# Imager_Mainboard.net
KiCad netlist of a schematic drawn in EAGLE
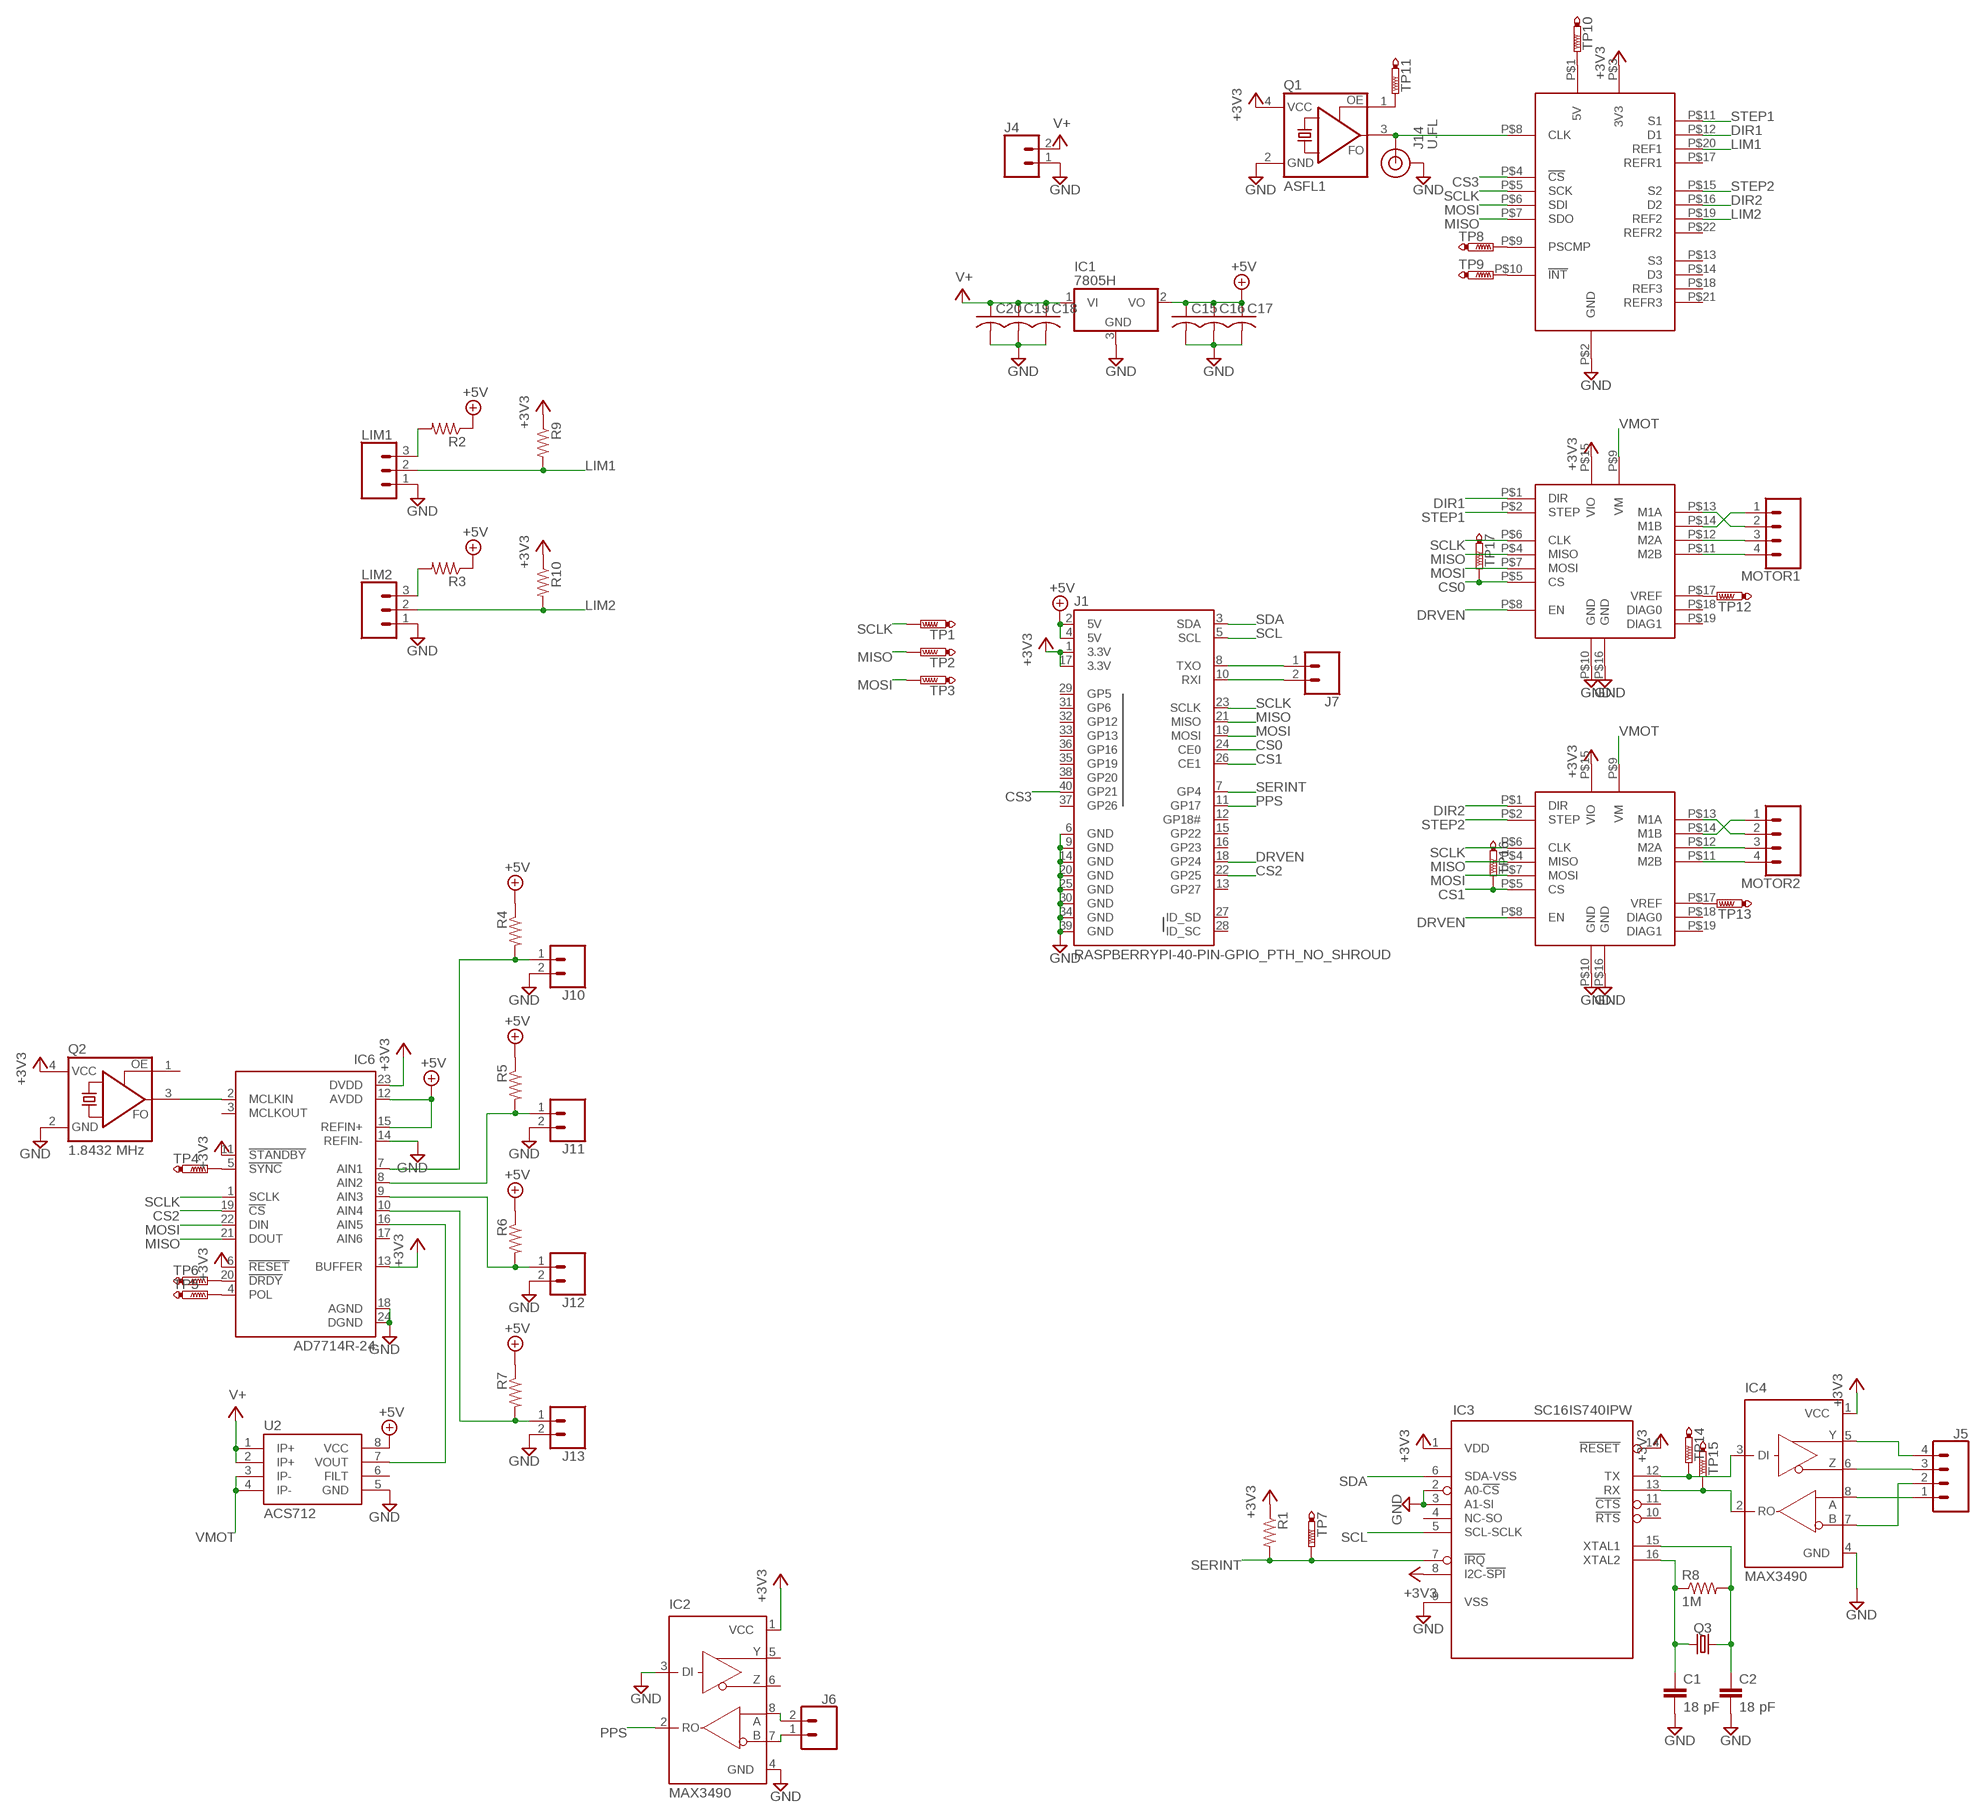
[diagram p0: schematic, sheet 1]

(export (version "E")
  (design (tool "Eeschema 10.0.6"))
  (components
    (comp (ref "C1")
      (value "18 pF")
      (footprint "eagle-import:C1206")
      (libsource (lib "eagle-import") (part "C-EUC1206"))
    )
    (comp (ref "C2")
      (value "18 pF")
      (footprint "eagle-import:C1206")
      (libsource (lib "eagle-import") (part "C-EUC1206"))
    )
    (comp (ref "C15")
      (value "C-USC1206")
      (footprint "eagle-import:C1206")
      (libsource (lib "eagle-import") (part "C-USC1206"))
    )
    (comp (ref "C16")
      (value "C-USC1206")
      (footprint "eagle-import:C1206")
      (libsource (lib "eagle-import") (part "C-USC1206"))
    )
    (comp (ref "C17")
      (value "C-USC1206")
      (footprint "eagle-import:C1206")
      (libsource (lib "eagle-import") (part "C-USC1206"))
    )
    (comp (ref "C18")
      (value "C-USC1206")
      (footprint "eagle-import:C1206")
      (libsource (lib "eagle-import") (part "C-USC1206"))
    )
    (comp (ref "C19")
      (value "C-USC1206")
      (footprint "eagle-import:C1206")
      (libsource (lib "eagle-import") (part "C-USC1206"))
    )
    (comp (ref "C20")
      (value "C-USC1206")
      (footprint "eagle-import:C1206")
      (libsource (lib "eagle-import") (part "C-USC1206"))
    )
    (comp (ref "DRV1")
      (value "SILENTSTEPSTICK")
      (footprint "eagle-import:SILENTSTEPSTICK")
      (libsource (lib "eagle-import") (part "SILENTSTEPSTICK"))
    )
    (comp (ref "DRV2")
      (value "SILENTSTEPSTICK")
      (footprint "eagle-import:SILENTSTEPSTICK")
      (libsource (lib "eagle-import") (part "SILENTSTEPSTICK"))
    )
    (comp (ref "IC1")
      (value "7805H")
      (footprint "eagle-import:TO39")
      (libsource (lib "eagle-import") (part "78H05"))
    )
    (comp (ref "IC2")
      (value "MAX3490")
      (footprint "eagle-import:SO08")
      (libsource (lib "eagle-import") (part "MAX3467PAC"))
    )
    (comp (ref "IC3")
      (value "SC16IS740IPW")
      (footprint "eagle-import:TSSOP16L")
      (libsource (lib "eagle-import") (part "SC16IS740IPW"))
    )
    (comp (ref "IC4")
      (value "MAX3490")
      (footprint "eagle-import:SO08")
      (libsource (lib "eagle-import") (part "MAX3467PAC"))
    )
    (comp (ref "IC6")
      (value "AD7714R-24")
      (footprint "eagle-import:SO24R")
      (libsource (lib "eagle-import") (part "AD7714R-24"))
    )
    (comp (ref "J1")
      (value "RASPBERRYPI-40-PIN-GPIO_PTH_NO_SHROUD")
      (footprint "eagle-import:2X20")
      (libsource (lib "eagle-import") (part "RASPBERRYPI-40-PIN-GPIO_PTH_NO_SHROUD"))
    )
    (comp (ref "J4")
      (value "CONN_02")
      (footprint "eagle-import:1X02")
      (libsource (lib "eagle-import") (part "CONN_02"))
    )
    (comp (ref "J5")
      (value "CONN_04")
      (footprint "eagle-import:1X04")
      (libsource (lib "eagle-import") (part "CONN_04"))
    )
    (comp (ref "J6")
      (value "CONN_02")
      (footprint "eagle-import:1X02")
      (libsource (lib "eagle-import") (part "CONN_02"))
    )
    (comp (ref "J7")
      (value "CONN_02")
      (footprint "eagle-import:1X02")
      (libsource (lib "eagle-import") (part "CONN_02"))
    )
    (comp (ref "J10")
      (value "CONN_02")
      (footprint "eagle-import:1X02")
      (libsource (lib "eagle-import") (part "CONN_02"))
    )
    (comp (ref "J11")
      (value "CONN_02")
      (footprint "eagle-import:1X02")
      (libsource (lib "eagle-import") (part "CONN_02"))
    )
    (comp (ref "J12")
      (value "CONN_02")
      (footprint "eagle-import:1X02")
      (libsource (lib "eagle-import") (part "CONN_02"))
    )
    (comp (ref "J13")
      (value "CONN_02")
      (footprint "eagle-import:1X02")
      (libsource (lib "eagle-import") (part "CONN_02"))
    )
    (comp (ref "J14")
      (value "U.FL")
      (footprint "eagle-import:U.FL")
      (libsource (lib "eagle-import") (part "U.FL2PIN"))
    )
    (comp (ref "LIM1")
      (value "CONN_03")
      (footprint "eagle-import:1X03")
      (libsource (lib "eagle-import") (part "CONN_03"))
    )
    (comp (ref "LIM2")
      (value "CONN_03")
      (footprint "eagle-import:1X03")
      (libsource (lib "eagle-import") (part "CONN_03"))
    )
    (comp (ref "MOTOR1")
      (value "CONN_04")
      (footprint "eagle-import:1X04")
      (libsource (lib "eagle-import") (part "CONN_04"))
    )
    (comp (ref "MOTOR2")
      (value "CONN_04")
      (footprint "eagle-import:1X04")
      (libsource (lib "eagle-import") (part "CONN_04"))
    )
    (comp (ref "Q1")
      (value "ASFL1")
      (footprint "eagle-import:ASF")
      (fields (field (name "MF") "Abracon Corporation") (field (name "MPN") "ASFL1-125.000MHZ-EC-T"))
      (libsource (lib "eagle-import") (part "ASFL1"))
    )
    (comp (ref "Q2")
      (value "1.8432 MHz")
      (footprint "eagle-import:ASF")
      (fields (field (name "MF") "Abracon Corporation") (field (name "MPN") "ASFL1-125.000MHZ-EC-T"))
      (libsource (lib "eagle-import") (part "ASFL1"))
    )
    (comp (ref "Q3")
      (value "CRYSTALSMD-5X3.2-4PAD")
      (footprint "eagle-import:CRYSTAL-SMD-5X3.2-4PAD")
      (libsource (lib "eagle-import") (part "CRYSTALSMD-5X3.2-4PAD"))
    )
    (comp (ref "R1")
      (value "R-US_R1206")
      (footprint "eagle-import:R1206")
      (libsource (lib "eagle-import") (part "R-US_R1206"))
    )
    (comp (ref "R2")
      (value "R-US_R1206")
      (footprint "eagle-import:R1206")
      (libsource (lib "eagle-import") (part "R-US_R1206"))
    )
    (comp (ref "R3")
      (value "R-US_R1206")
      (footprint "eagle-import:R1206")
      (libsource (lib "eagle-import") (part "R-US_R1206"))
    )
    (comp (ref "R4")
      (value "R-US_R1206")
      (footprint "eagle-import:R1206")
      (libsource (lib "eagle-import") (part "R-US_R1206"))
    )
    (comp (ref "R5")
      (value "R-US_R1206")
      (footprint "eagle-import:R1206")
      (libsource (lib "eagle-import") (part "R-US_R1206"))
    )
    (comp (ref "R6")
      (value "R-US_R1206")
      (footprint "eagle-import:R1206")
      (libsource (lib "eagle-import") (part "R-US_R1206"))
    )
    (comp (ref "R7")
      (value "R-US_R1206")
      (footprint "eagle-import:R1206")
      (libsource (lib "eagle-import") (part "R-US_R1206"))
    )
    (comp (ref "R8")
      (value "1M")
      (footprint "eagle-import:R1206")
      (libsource (lib "eagle-import") (part "R-US_R1206"))
    )
    (comp (ref "R9")
      (value "R-US_R1206")
      (footprint "eagle-import:R1206")
      (libsource (lib "eagle-import") (part "R-US_R1206"))
    )
    (comp (ref "R10")
      (value "R-US_R1206")
      (footprint "eagle-import:R1206")
      (libsource (lib "eagle-import") (part "R-US_R1206"))
    )
    (comp (ref "TP1")
      (value "PTR1PAD1-13")
      (footprint "eagle-import:P1-13")
      (libsource (lib "eagle-import") (part "PTR1PAD1-13"))
    )
    (comp (ref "TP2")
      (value "PTR1PAD1-13")
      (footprint "eagle-import:P1-13")
      (libsource (lib "eagle-import") (part "PTR1PAD1-13"))
    )
    (comp (ref "TP3")
      (value "PTR1PAD1-13")
      (footprint "eagle-import:P1-13")
      (libsource (lib "eagle-import") (part "PTR1PAD1-13"))
    )
    (comp (ref "TP4")
      (value "PTR1B1,27")
      (footprint "eagle-import:B1,27")
      (libsource (lib "eagle-import") (part "PTR1B1,27"))
    )
    (comp (ref "TP5")
      (value "PTR1B1,27")
      (footprint "eagle-import:B1,27")
      (libsource (lib "eagle-import") (part "PTR1B1,27"))
    )
    (comp (ref "TP6")
      (value "PTR1B1,27")
      (footprint "eagle-import:B1,27")
      (libsource (lib "eagle-import") (part "PTR1B1,27"))
    )
    (comp (ref "TP7")
      (value "PTR1B1,27")
      (footprint "eagle-import:B1,27")
      (libsource (lib "eagle-import") (part "PTR1B1,27"))
    )
    (comp (ref "TP8")
      (value "PTR1PAD1-13")
      (footprint "eagle-import:P1-13")
      (libsource (lib "eagle-import") (part "PTR1PAD1-13"))
    )
    (comp (ref "TP9")
      (value "PTR1PAD1-13")
      (footprint "eagle-import:P1-13")
      (libsource (lib "eagle-import") (part "PTR1PAD1-13"))
    )
    (comp (ref "TP10")
      (value "PTR1PAD1-13")
      (footprint "eagle-import:P1-13")
      (libsource (lib "eagle-import") (part "PTR1PAD1-13"))
    )
    (comp (ref "TP11")
      (value "PTR1PAD1-13")
      (footprint "eagle-import:P1-13")
      (libsource (lib "eagle-import") (part "PTR1PAD1-13"))
    )
    (comp (ref "TP12")
      (value "PTR1PAD1-13")
      (footprint "eagle-import:P1-13")
      (libsource (lib "eagle-import") (part "PTR1PAD1-13"))
    )
    (comp (ref "TP13")
      (value "PTR1PAD1-13")
      (footprint "eagle-import:P1-13")
      (libsource (lib "eagle-import") (part "PTR1PAD1-13"))
    )
    (comp (ref "TP14")
      (value "PTR1PAD1-13")
      (footprint "eagle-import:P1-13")
      (libsource (lib "eagle-import") (part "PTR1PAD1-13"))
    )
    (comp (ref "TP15")
      (value "PTR1PAD1-13")
      (footprint "eagle-import:P1-13")
      (libsource (lib "eagle-import") (part "PTR1PAD1-13"))
    )
    (comp (ref "TP16")
      (value "PTR1PAD1-13")
      (footprint "eagle-import:P1-13")
      (libsource (lib "eagle-import") (part "PTR1PAD1-13"))
    )
    (comp (ref "TP17")
      (value "PTR1PAD1-13")
      (footprint "eagle-import:P1-13")
      (libsource (lib "eagle-import") (part "PTR1PAD1-13"))
    )
    (comp (ref "U$1")
      (value "TMC429-BOB")
      (footprint "eagle-import:TMC429-BOB")
      (libsource (lib "eagle-import") (part "TMC429-BOB"))
    )
    (comp (ref "U2")
      (value "ACS712")
      (footprint "eagle-import:SO08")
      (libsource (lib "eagle-import") (part "ACS712"))
    )
  )
  (nets
    (net (code "1") (name "+3V3") (class "Default")
      (node (ref "DRV1") (pin "P$15") (pinfunction "VIO_P$15") (pintype "bidirectional"))
      (node (ref "DRV2") (pin "P$15") (pinfunction "VIO_P$15") (pintype "bidirectional"))
      (node (ref "IC2") (pin "1") (pinfunction "VCC_1") (pintype "power_in"))
      (node (ref "IC3") (pin "1") (pinfunction "VDD_1") (pintype "bidirectional"))
      (node (ref "IC3") (pin "14") (pinfunction "~{RESET}_14") (pintype "bidirectional"))
      (node (ref "IC3") (pin "8") (pinfunction "I2C-~{SPI}_8") (pintype "bidirectional"))
      (node (ref "IC4") (pin "1") (pinfunction "VCC_1") (pintype "power_in"))
      (node (ref "IC6") (pin "11") (pinfunction "~{STANDBY}_11") (pintype "input"))
      (node (ref "IC6") (pin "13") (pinfunction "BUFFER_13") (pintype "input"))
      (node (ref "IC6") (pin "23") (pinfunction "DVDD_23") (pintype "input"))
      (node (ref "IC6") (pin "6") (pinfunction "~{RESET}_6") (pintype "input"))
      (node (ref "J1") (pin "1") (pinfunction "3.3V_1") (pintype "power_in"))
      (node (ref "J1") (pin "17") (pinfunction "3.3V_17") (pintype "power_in"))
      (node (ref "Q1") (pin "4") (pinfunction "VCC_4") (pintype "power_in"))
      (node (ref "Q2") (pin "4") (pinfunction "VCC_4") (pintype "power_in"))
      (node (ref "R1") (pin "1") (pinfunction "1_1") (pintype "passive"))
      (node (ref "R10") (pin "1") (pinfunction "1_1") (pintype "passive"))
      (node (ref "R9") (pin "1") (pinfunction "1_1") (pintype "passive"))
      (node (ref "U$1") (pin "P$3") (pinfunction "3V3_P$3") (pintype "bidirectional"))
    )
    (net (code "2") (name "+5V") (class "Default")
      (node (ref "C15") (pin "1") (pinfunction "1_1") (pintype "passive"))
      (node (ref "C16") (pin "1") (pinfunction "1_1") (pintype "passive"))
      (node (ref "C17") (pin "1") (pinfunction "1_1") (pintype "passive"))
      (node (ref "IC1") (pin "2") (pinfunction "VO_2") (pintype "passive"))
      (node (ref "IC6") (pin "12") (pinfunction "AVDD_12") (pintype "input"))
      (node (ref "IC6") (pin "15") (pinfunction "REFIN+_15") (pintype "input"))
      (node (ref "J1") (pin "2") (pinfunction "5V_2") (pintype "power_in"))
      (node (ref "J1") (pin "4") (pinfunction "5V_4") (pintype "power_in"))
      (node (ref "R2") (pin "1") (pinfunction "1_1") (pintype "passive"))
      (node (ref "R3") (pin "1") (pinfunction "1_1") (pintype "passive"))
      (node (ref "R4") (pin "1") (pinfunction "1_1") (pintype "passive"))
      (node (ref "R5") (pin "1") (pinfunction "1_1") (pintype "passive"))
      (node (ref "R6") (pin "1") (pinfunction "1_1") (pintype "passive"))
      (node (ref "R7") (pin "1") (pinfunction "1_1") (pintype "passive"))
      (node (ref "U2") (pin "8") (pinfunction "VCC_8") (pintype "bidirectional"))
    )
    (net (code "3") (name "/CS0") (class "Default")
      (node (ref "DRV1") (pin "P$5") (pinfunction "CS_P$5") (pintype "bidirectional"))
      (node (ref "J1") (pin "24") (pinfunction "CE0_24") (pintype "output"))
      (node (ref "TP17") (pin "TP") (pinfunction "TP_TP") (pintype "input"))
    )
    (net (code "4") (name "/CS1") (class "Default")
      (node (ref "DRV2") (pin "P$5") (pinfunction "CS_P$5") (pintype "bidirectional"))
      (node (ref "J1") (pin "26") (pinfunction "CE1_26") (pintype "output"))
      (node (ref "TP16") (pin "TP") (pinfunction "TP_TP") (pintype "input"))
    )
    (net (code "5") (name "/CS2") (class "Default")
      (node (ref "IC6") (pin "19") (pinfunction "~{CS}_19") (pintype "input"))
      (node (ref "J1") (pin "22") (pinfunction "GP25_22") (pintype "bidirectional"))
    )
    (net (code "6") (name "/CS3") (class "Default")
      (node (ref "J1") (pin "40") (pinfunction "GP21_40") (pintype "bidirectional"))
      (node (ref "U$1") (pin "P$4") (pinfunction "~{CS}_P$4") (pintype "bidirectional"))
    )
    (net (code "7") (name "/DIR1") (class "Default")
      (node (ref "DRV1") (pin "P$1") (pinfunction "DIR_P$1") (pintype "bidirectional"))
      (node (ref "U$1") (pin "P$12") (pinfunction "D1_P$12") (pintype "bidirectional"))
    )
    (net (code "8") (name "/DIR2") (class "Default")
      (node (ref "DRV2") (pin "P$1") (pinfunction "DIR_P$1") (pintype "bidirectional"))
      (node (ref "U$1") (pin "P$16") (pinfunction "D2_P$16") (pintype "bidirectional"))
    )
    (net (code "9") (name "/DRVEN") (class "Default")
      (node (ref "DRV1") (pin "P$8") (pinfunction "EN_P$8") (pintype "bidirectional"))
      (node (ref "DRV2") (pin "P$8") (pinfunction "EN_P$8") (pintype "bidirectional"))
      (node (ref "J1") (pin "18") (pinfunction "GP24_18") (pintype "bidirectional"))
    )
    (net (code "10") (name "/LIM1") (class "Default")
      (node (ref "LIM1") (pin "2") (pinfunction "2_2") (pintype "passive"))
      (node (ref "R9") (pin "2") (pinfunction "2_2") (pintype "passive"))
      (node (ref "U$1") (pin "P$20") (pinfunction "REF1_P$20") (pintype "bidirectional"))
    )
    (net (code "11") (name "/LIM2") (class "Default")
      (node (ref "LIM2") (pin "2") (pinfunction "2_2") (pintype "passive"))
      (node (ref "R10") (pin "2") (pinfunction "2_2") (pintype "passive"))
      (node (ref "U$1") (pin "P$19") (pinfunction "REF2_P$19") (pintype "bidirectional"))
    )
    (net (code "12") (name "/MISO") (class "Default")
      (node (ref "DRV1") (pin "P$4") (pinfunction "MISO_P$4") (pintype "bidirectional"))
      (node (ref "DRV2") (pin "P$4") (pinfunction "MISO_P$4") (pintype "bidirectional"))
      (node (ref "IC6") (pin "21") (pinfunction "DOUT_21") (pintype "output"))
      (node (ref "J1") (pin "21") (pinfunction "MISO_21") (pintype "input"))
      (node (ref "TP2") (pin "TP") (pinfunction "TP_TP") (pintype "input"))
      (node (ref "U$1") (pin "P$7") (pinfunction "SDO_P$7") (pintype "bidirectional"))
    )
    (net (code "13") (name "/MOSI") (class "Default")
      (node (ref "DRV1") (pin "P$7") (pinfunction "MOSI_P$7") (pintype "bidirectional"))
      (node (ref "DRV2") (pin "P$7") (pinfunction "MOSI_P$7") (pintype "bidirectional"))
      (node (ref "IC6") (pin "22") (pinfunction "DIN_22") (pintype "input"))
      (node (ref "J1") (pin "19") (pinfunction "MOSI_19") (pintype "output"))
      (node (ref "TP3") (pin "TP") (pinfunction "TP_TP") (pintype "input"))
      (node (ref "U$1") (pin "P$6") (pinfunction "SDI_P$6") (pintype "bidirectional"))
    )
    (net (code "14") (name "/PPS") (class "Default")
      (node (ref "IC2") (pin "2") (pinfunction "RO_2") (pintype "output"))
      (node (ref "J1") (pin "11") (pinfunction "GP17_11") (pintype "bidirectional"))
    )
    (net (code "15") (name "/SCL") (class "Default")
      (node (ref "IC3") (pin "5") (pinfunction "SCL-SCLK_5") (pintype "bidirectional"))
      (node (ref "J1") (pin "5") (pinfunction "SCL_5") (pintype "bidirectional"))
    )
    (net (code "16") (name "/SCLK") (class "Default")
      (node (ref "DRV1") (pin "P$6") (pinfunction "CLK_P$6") (pintype "bidirectional"))
      (node (ref "DRV2") (pin "P$6") (pinfunction "CLK_P$6") (pintype "bidirectional"))
      (node (ref "IC6") (pin "1") (pinfunction "SCLK_1") (pintype "input"))
      (node (ref "J1") (pin "23") (pinfunction "SCLK_23") (pintype "output"))
      (node (ref "TP1") (pin "TP") (pinfunction "TP_TP") (pintype "input"))
      (node (ref "U$1") (pin "P$5") (pinfunction "SCK_P$5") (pintype "bidirectional"))
    )
    (net (code "17") (name "/SDA") (class "Default")
      (node (ref "IC3") (pin "6") (pinfunction "SDA-VSS_6") (pintype "bidirectional"))
      (node (ref "J1") (pin "3") (pinfunction "SDA_3") (pintype "bidirectional"))
    )
    (net (code "18") (name "/SERINT") (class "Default")
      (node (ref "IC3") (pin "7") (pinfunction "~{IRQ}_7") (pintype "bidirectional"))
      (node (ref "J1") (pin "7") (pinfunction "GP4_7") (pintype "bidirectional"))
      (node (ref "R1") (pin "2") (pinfunction "2_2") (pintype "passive"))
      (node (ref "TP7") (pin "TP") (pinfunction "TP_TP") (pintype "input"))
    )
    (net (code "19") (name "/STEP1") (class "Default")
      (node (ref "DRV1") (pin "P$2") (pinfunction "STEP_P$2") (pintype "bidirectional"))
      (node (ref "U$1") (pin "P$11") (pinfunction "S1_P$11") (pintype "bidirectional"))
    )
    (net (code "20") (name "/STEP2") (class "Default")
      (node (ref "DRV2") (pin "P$2") (pinfunction "STEP_P$2") (pintype "bidirectional"))
      (node (ref "U$1") (pin "P$15") (pinfunction "S2_P$15") (pintype "bidirectional"))
    )
    (net (code "21") (name "/VMOT") (class "Default")
      (node (ref "DRV1") (pin "P$9") (pinfunction "VM_P$9") (pintype "bidirectional"))
      (node (ref "DRV2") (pin "P$9") (pinfunction "VM_P$9") (pintype "bidirectional"))
      (node (ref "U2") (pin "3") (pinfunction "IP-_3") (pintype "bidirectional"))
      (node (ref "U2") (pin "4") (pinfunction "IP-_4") (pintype "bidirectional"))
    )
    (net (code "22") (name "GND") (class "Default")
      (node (ref "C1") (pin "2") (pinfunction "2_2") (pintype "passive"))
      (node (ref "C15") (pin "2") (pinfunction "2_2") (pintype "passive"))
      (node (ref "C16") (pin "2") (pinfunction "2_2") (pintype "passive"))
      (node (ref "C17") (pin "2") (pinfunction "2_2") (pintype "passive"))
      (node (ref "C18") (pin "2") (pinfunction "2_2") (pintype "passive"))
      (node (ref "C19") (pin "2") (pinfunction "2_2") (pintype "passive"))
      (node (ref "C2") (pin "2") (pinfunction "2_2") (pintype "passive"))
      (node (ref "C20") (pin "2") (pinfunction "2_2") (pintype "passive"))
      (node (ref "DRV1") (pin "P$10") (pinfunction "GND_P$10") (pintype "bidirectional"))
      (node (ref "DRV1") (pin "P$16") (pinfunction "GND_P$16") (pintype "bidirectional"))
      (node (ref "DRV2") (pin "P$10") (pinfunction "GND_P$10") (pintype "bidirectional"))
      (node (ref "DRV2") (pin "P$16") (pinfunction "GND_P$16") (pintype "bidirectional"))
      (node (ref "IC1") (pin "3") (pinfunction "GND_3") (pintype "passive"))
      (node (ref "IC2") (pin "3") (pinfunction "DI_3") (pintype "input"))
      (node (ref "IC2") (pin "4") (pinfunction "GND_4") (pintype "power_in"))
      (node (ref "IC3") (pin "2") (pinfunction "A0-~{CS}_2") (pintype "bidirectional"))
      (node (ref "IC3") (pin "3") (pinfunction "A1-SI_3") (pintype "bidirectional"))
      (node (ref "IC3") (pin "9") (pinfunction "VSS_9") (pintype "bidirectional"))
      (node (ref "IC4") (pin "4") (pinfunction "GND_4") (pintype "power_in"))
      (node (ref "IC6") (pin "14") (pinfunction "REFIN-_14") (pintype "input"))
      (node (ref "IC6") (pin "18") (pinfunction "AGND_18") (pintype "input"))
      (node (ref "IC6") (pin "24") (pinfunction "DGND_24") (pintype "input"))
      (node (ref "J1") (pin "14") (pinfunction "GND_14") (pintype "power_in"))
      (node (ref "J1") (pin "20") (pinfunction "GND_20") (pintype "power_in"))
      (node (ref "J1") (pin "25") (pinfunction "GND_25") (pintype "power_in"))
      (node (ref "J1") (pin "30") (pinfunction "GND_30") (pintype "power_in"))
      (node (ref "J1") (pin "34") (pinfunction "GND_34") (pintype "power_in"))
      (node (ref "J1") (pin "39") (pinfunction "GND_39") (pintype "power_in"))
      (node (ref "J1") (pin "6") (pinfunction "GND_6") (pintype "power_in"))
      (node (ref "J1") (pin "9") (pinfunction "GND_9") (pintype "power_in"))
      (node (ref "J10") (pin "2") (pinfunction "2_2") (pintype "passive"))
      (node (ref "J11") (pin "2") (pinfunction "2_2") (pintype "passive"))
      (node (ref "J12") (pin "2") (pinfunction "2_2") (pintype "passive"))
      (node (ref "J13") (pin "2") (pinfunction "2_2") (pintype "passive"))
      (node (ref "J14") (pin "1") (pinfunction "GND_1") (pintype "bidirectional"))
      (node (ref "J14") (pin "2") (pinfunction "GND_2") (pintype "bidirectional"))
      (node (ref "J4") (pin "1") (pinfunction "1_1") (pintype "passive"))
      (node (ref "LIM1") (pin "1") (pinfunction "1_1") (pintype "passive"))
      (node (ref "LIM2") (pin "1") (pinfunction "1_1") (pintype "passive"))
      (node (ref "Q1") (pin "2") (pinfunction "GND_2") (pintype "power_in"))
      (node (ref "Q2") (pin "2") (pinfunction "GND_2") (pintype "power_in"))
      (node (ref "U$1") (pin "P$2") (pinfunction "GND_P$2") (pintype "bidirectional"))
      (node (ref "U2") (pin "5") (pinfunction "GND_5") (pintype "bidirectional"))
    )
    (net (code "23") (name "Net-(DRV1-M1A)") (class "Default")
      (node (ref "DRV1") (pin "P$13") (pinfunction "M1A_P$13") (pintype "bidirectional"))
      (node (ref "MOTOR1") (pin "2") (pinfunction "2_2") (pintype "passive"))
    )
    (net (code "24") (name "Net-(DRV1-M1B)") (class "Default")
      (node (ref "DRV1") (pin "P$14") (pinfunction "M1B_P$14") (pintype "bidirectional"))
      (node (ref "MOTOR1") (pin "1") (pinfunction "1_1") (pintype "passive"))
    )
    (net (code "25") (name "Net-(DRV1-M2A)") (class "Default")
      (node (ref "DRV1") (pin "P$12") (pinfunction "M2A_P$12") (pintype "bidirectional"))
      (node (ref "MOTOR1") (pin "3") (pinfunction "3_3") (pintype "passive"))
    )
    (net (code "26") (name "Net-(DRV1-M2B)") (class "Default")
      (node (ref "DRV1") (pin "P$11") (pinfunction "M2B_P$11") (pintype "bidirectional"))
      (node (ref "MOTOR1") (pin "4") (pinfunction "4_4") (pintype "passive"))
    )
    (net (code "27") (name "Net-(DRV1-VREF)") (class "Default")
      (node (ref "DRV1") (pin "P$17") (pinfunction "VREF_P$17") (pintype "bidirectional"))
      (node (ref "TP12") (pin "TP") (pinfunction "TP_TP") (pintype "input"))
    )
    (net (code "28") (name "Net-(DRV2-M1A)") (class "Default")
      (node (ref "DRV2") (pin "P$13") (pinfunction "M1A_P$13") (pintype "bidirectional"))
      (node (ref "MOTOR2") (pin "2") (pinfunction "2_2") (pintype "passive"))
    )
    (net (code "29") (name "Net-(DRV2-M1B)") (class "Default")
      (node (ref "DRV2") (pin "P$14") (pinfunction "M1B_P$14") (pintype "bidirectional"))
      (node (ref "MOTOR2") (pin "1") (pinfunction "1_1") (pintype "passive"))
    )
    (net (code "30") (name "Net-(DRV2-M2A)") (class "Default")
      (node (ref "DRV2") (pin "P$12") (pinfunction "M2A_P$12") (pintype "bidirectional"))
      (node (ref "MOTOR2") (pin "3") (pinfunction "3_3") (pintype "passive"))
    )
    (net (code "31") (name "Net-(DRV2-M2B)") (class "Default")
      (node (ref "DRV2") (pin "P$11") (pinfunction "M2B_P$11") (pintype "bidirectional"))
      (node (ref "MOTOR2") (pin "4") (pinfunction "4_4") (pintype "passive"))
    )
    (net (code "32") (name "Net-(DRV2-VREF)") (class "Default")
      (node (ref "DRV2") (pin "P$17") (pinfunction "VREF_P$17") (pintype "bidirectional"))
      (node (ref "TP13") (pin "TP") (pinfunction "TP_TP") (pintype "input"))
    )
    (net (code "33") (name "Net-(IC2-A)") (class "Default")
      (node (ref "IC2") (pin "8") (pinfunction "A_8") (pintype "passive"))
      (node (ref "J6") (pin "2") (pinfunction "2_2") (pintype "passive"))
    )
    (net (code "34") (name "Net-(IC2-B)") (class "Default")
      (node (ref "IC2") (pin "7") (pinfunction "B_7") (pintype "passive"))
      (node (ref "J6") (pin "1") (pinfunction "1_1") (pintype "passive"))
    )
    (net (code "35") (name "Net-(IC3-RX)") (class "Default")
      (node (ref "IC3") (pin "13") (pinfunction "RX_13") (pintype "bidirectional"))
      (node (ref "IC4") (pin "2") (pinfunction "RO_2") (pintype "output"))
      (node (ref "TP15") (pin "TP") (pinfunction "TP_TP") (pintype "input"))
    )
    (net (code "36") (name "Net-(IC3-TX)") (class "Default")
      (node (ref "IC3") (pin "12") (pinfunction "TX_12") (pintype "bidirectional"))
      (node (ref "IC4") (pin "3") (pinfunction "DI_3") (pintype "input"))
      (node (ref "TP14") (pin "TP") (pinfunction "TP_TP") (pintype "input"))
    )
    (net (code "37") (name "Net-(IC3-XTAL1)") (class "Default")
      (node (ref "C2") (pin "1") (pinfunction "1_1") (pintype "passive"))
      (node (ref "IC3") (pin "15") (pinfunction "XTAL1_15") (pintype "bidirectional"))
      (node (ref "Q3") (pin "3") (pinfunction "2_3") (pintype "passive"))
      (node (ref "R8") (pin "2") (pinfunction "2_2") (pintype "passive"))
    )
    (net (code "38") (name "Net-(IC3-XTAL2)") (class "Default")
      (node (ref "C1") (pin "1") (pinfunction "1_1") (pintype "passive"))
      (node (ref "IC3") (pin "16") (pinfunction "XTAL2_16") (pintype "bidirectional"))
      (node (ref "Q3") (pin "1") (pinfunction "1_1") (pintype "passive"))
      (node (ref "R8") (pin "1") (pinfunction "1_1") (pintype "passive"))
    )
    (net (code "39") (name "Net-(IC4-A)") (class "Default")
      (node (ref "IC4") (pin "8") (pinfunction "A_8") (pintype "passive"))
      (node (ref "J5") (pin "1") (pinfunction "1_1") (pintype "passive"))
    )
    (net (code "40") (name "Net-(IC4-B)") (class "Default")
      (node (ref "IC4") (pin "7") (pinfunction "B_7") (pintype "passive"))
      (node (ref "J5") (pin "2") (pinfunction "2_2") (pintype "passive"))
    )
    (net (code "41") (name "Net-(IC4-Y)") (class "Default")
      (node (ref "IC4") (pin "5") (pinfunction "Y_5") (pintype "passive"))
      (node (ref "J5") (pin "4") (pinfunction "4_4") (pintype "passive"))
    )
    (net (code "42") (name "Net-(IC4-Z)") (class "Default")
      (node (ref "IC4") (pin "6") (pinfunction "Z_6") (pintype "passive"))
      (node (ref "J5") (pin "3") (pinfunction "3_3") (pintype "passive"))
    )
    (net (code "43") (name "Net-(IC6-AIN1)") (class "Default")
      (node (ref "IC6") (pin "7") (pinfunction "AIN1_7") (pintype "input"))
      (node (ref "J10") (pin "1") (pinfunction "1_1") (pintype "passive"))
      (node (ref "R4") (pin "2") (pinfunction "2_2") (pintype "passive"))
    )
    (net (code "44") (name "Net-(IC6-AIN2)") (class "Default")
      (node (ref "IC6") (pin "8") (pinfunction "AIN2_8") (pintype "input"))
      (node (ref "J11") (pin "1") (pinfunction "1_1") (pintype "passive"))
      (node (ref "R5") (pin "2") (pinfunction "2_2") (pintype "passive"))
    )
    (net (code "45") (name "Net-(IC6-AIN3)") (class "Default")
      (node (ref "IC6") (pin "9") (pinfunction "AIN3_9") (pintype "input"))
      (node (ref "J12") (pin "1") (pinfunction "1_1") (pintype "passive"))
      (node (ref "R6") (pin "2") (pinfunction "2_2") (pintype "passive"))
    )
    (net (code "46") (name "Net-(IC6-AIN4)") (class "Default")
      (node (ref "IC6") (pin "10") (pinfunction "AIN4_10") (pintype "input"))
      (node (ref "J13") (pin "1") (pinfunction "1_1") (pintype "passive"))
      (node (ref "R7") (pin "2") (pinfunction "2_2") (pintype "passive"))
    )
    (net (code "47") (name "Net-(IC6-AIN5)") (class "Default")
      (node (ref "IC6") (pin "16") (pinfunction "AIN5_16") (pintype "input"))
      (node (ref "U2") (pin "7") (pinfunction "VOUT_7") (pintype "bidirectional"))
    )
    (net (code "48") (name "Net-(IC6-MCLKIN)") (class "Default")
      (node (ref "IC6") (pin "2") (pinfunction "MCLKIN_2") (pintype "input"))
      (node (ref "Q2") (pin "3") (pinfunction "FO_3") (pintype "output"))
    )
    (net (code "49") (name "Net-(IC6-POL)") (class "Default")
      (node (ref "IC6") (pin "4") (pinfunction "POL_4") (pintype "input"))
      (node (ref "TP5") (pin "TP") (pinfunction "TP_TP") (pintype "input"))
    )
    (net (code "50") (name "Net-(IC6-~{DRDY})") (class "Default")
      (node (ref "IC6") (pin "20") (pinfunction "~{DRDY}_20") (pintype "input"))
      (node (ref "TP6") (pin "TP") (pinfunction "TP_TP") (pintype "input"))
    )
    (net (code "51") (name "Net-(IC6-~{SYNC})") (class "Default")
      (node (ref "IC6") (pin "5") (pinfunction "~{SYNC}_5") (pintype "input"))
      (node (ref "TP4") (pin "TP") (pinfunction "TP_TP") (pintype "input"))
    )
    (net (code "52") (name "Net-(J1-RXI)") (class "Default")
      (node (ref "J1") (pin "10") (pinfunction "RXI_10") (pintype "input"))
      (node (ref "J7") (pin "2") (pinfunction "2_2") (pintype "passive"))
    )
    (net (code "53") (name "Net-(J1-TXO)") (class "Default")
      (node (ref "J1") (pin "8") (pinfunction "TXO_8") (pintype "output"))
      (node (ref "J7") (pin "1") (pinfunction "1_1") (pintype "passive"))
    )
    (net (code "54") (name "Net-(J14-SIGNAL)") (class "Default")
      (node (ref "J14") (pin "FEED") (pinfunction "SIGNAL_FEED") (pintype "bidirectional"))
      (node (ref "Q1") (pin "3") (pinfunction "FO_3") (pintype "output"))
      (node (ref "U$1") (pin "P$8") (pinfunction "CLK_P$8") (pintype "bidirectional"))
    )
    (net (code "55") (name "Net-(LIM1-Pad3)") (class "Default")
      (node (ref "LIM1") (pin "3") (pinfunction "3_3") (pintype "passive"))
      (node (ref "R2") (pin "2") (pinfunction "2_2") (pintype "passive"))
    )
    (net (code "56") (name "Net-(LIM2-Pad3)") (class "Default")
      (node (ref "LIM2") (pin "3") (pinfunction "3_3") (pintype "passive"))
      (node (ref "R3") (pin "2") (pinfunction "2_2") (pintype "passive"))
    )
    (net (code "57") (name "Net-(Q1-OE)") (class "Default")
      (node (ref "Q1") (pin "1") (pinfunction "OE_1") (pintype "input"))
      (node (ref "TP11") (pin "TP") (pinfunction "TP_TP") (pintype "input"))
    )
    (net (code "58") (name "Net-(U$1-5V)") (class "Default")
      (node (ref "TP10") (pin "TP") (pinfunction "TP_TP") (pintype "input"))
      (node (ref "U$1") (pin "P$1") (pinfunction "5V_P$1") (pintype "bidirectional"))
    )
    (net (code "59") (name "Net-(U$1-PSCMP)") (class "Default")
      (node (ref "TP8") (pin "TP") (pinfunction "TP_TP") (pintype "input"))
      (node (ref "U$1") (pin "P$9") (pinfunction "PSCMP_P$9") (pintype "bidirectional"))
    )
    (net (code "60") (name "Net-(U$1-~{INT})") (class "Default")
      (node (ref "TP9") (pin "TP") (pinfunction "TP_TP") (pintype "input"))
      (node (ref "U$1") (pin "P$10") (pinfunction "~{INT}_P$10") (pintype "bidirectional"))
    )
    (net (code "61") (name "V+") (class "Default")
      (node (ref "C18") (pin "1") (pinfunction "1_1") (pintype "passive"))
      (node (ref "C19") (pin "1") (pinfunction "1_1") (pintype "passive"))
      (node (ref "C20") (pin "1") (pinfunction "1_1") (pintype "passive"))
      (node (ref "IC1") (pin "1") (pinfunction "VI_1") (pintype "input"))
      (node (ref "J4") (pin "2") (pinfunction "2_2") (pintype "passive"))
      (node (ref "U2") (pin "1") (pinfunction "IP+_1") (pintype "bidirectional"))
      (node (ref "U2") (pin "2") (pinfunction "IP+_2") (pintype "bidirectional"))
    )
    (net (code "62") (name "unconnected-(DRV1-DIAG0-PadP$18)") (class "Default")
      (node (ref "DRV1") (pin "P$18") (pinfunction "DIAG0_P$18") (pintype "bidirectional"))
    )
    (net (code "63") (name "unconnected-(DRV1-DIAG1-PadP$19)") (class "Default")
      (node (ref "DRV1") (pin "P$19") (pinfunction "DIAG1_P$19") (pintype "bidirectional"))
    )
    (net (code "64") (name "unconnected-(DRV2-DIAG0-PadP$18)") (class "Default")
      (node (ref "DRV2") (pin "P$18") (pinfunction "DIAG0_P$18") (pintype "bidirectional"))
    )
    (net (code "65") (name "unconnected-(DRV2-DIAG1-PadP$19)") (class "Default")
      (node (ref "DRV2") (pin "P$19") (pinfunction "DIAG1_P$19") (pintype "bidirectional"))
    )
    (net (code "66") (name "unconnected-(IC2-Y-Pad5)") (class "Default")
      (node (ref "IC2") (pin "5") (pinfunction "Y_5") (pintype "passive"))
    )
    (net (code "67") (name "unconnected-(IC2-Z-Pad6)") (class "Default")
      (node (ref "IC2") (pin "6") (pinfunction "Z_6") (pintype "passive"))
    )
    (net (code "68") (name "unconnected-(IC3-NC-SO-Pad4)") (class "Default")
      (node (ref "IC3") (pin "4") (pinfunction "NC-SO_4") (pintype "bidirectional"))
    )
    (net (code "69") (name "unconnected-(IC3-~{CTS}-Pad11)") (class "Default")
      (node (ref "IC3") (pin "11") (pinfunction "~{CTS}_11") (pintype "bidirectional"))
    )
    (net (code "70") (name "unconnected-(IC3-~{RTS}-Pad10)") (class "Default")
      (node (ref "IC3") (pin "10") (pinfunction "~{RTS}_10") (pintype "bidirectional"))
    )
    (net (code "71") (name "unconnected-(IC6-AIN6-Pad17)") (class "Default")
      (node (ref "IC6") (pin "17") (pinfunction "AIN6_17") (pintype "input"))
    )
    (net (code "72") (name "unconnected-(IC6-MCLKOUT-Pad3)") (class "Default")
      (node (ref "IC6") (pin "3") (pinfunction "MCLKOUT_3") (pintype "output"))
    )
    (net (code "73") (name "unconnected-(J1-GP5-Pad29)") (class "Default")
      (node (ref "J1") (pin "29") (pinfunction "GP5_29") (pintype "bidirectional"))
    )
    (net (code "74") (name "unconnected-(J1-GP6-Pad31)") (class "Default")
      (node (ref "J1") (pin "31") (pinfunction "GP6_31") (pintype "bidirectional"))
    )
    (net (code "75") (name "unconnected-(J1-GP12-Pad32)") (class "Default")
      (node (ref "J1") (pin "32") (pinfunction "GP12_32") (pintype "bidirectional"))
    )
    (net (code "76") (name "unconnected-(J1-GP13-Pad33)") (class "Default")
      (node (ref "J1") (pin "33") (pinfunction "GP13_33") (pintype "bidirectional"))
    )
    (net (code "77") (name "unconnected-(J1-GP16-Pad36)") (class "Default")
      (node (ref "J1") (pin "36") (pinfunction "GP16_36") (pintype "bidirectional"))
    )
    (net (code "78") (name "unconnected-(J1-GP18#-Pad12)") (class "Default")
      (node (ref "J1") (pin "12") (pinfunction "GP18#_12") (pintype "bidirectional"))
    )
    (net (code "79") (name "unconnected-(J1-GP19-Pad35)") (class "Default")
      (node (ref "J1") (pin "35") (pinfunction "GP19_35") (pintype "bidirectional"))
    )
    (net (code "80") (name "unconnected-(J1-GP20-Pad38)") (class "Default")
      (node (ref "J1") (pin "38") (pinfunction "GP20_38") (pintype "bidirectional"))
    )
    (net (code "81") (name "unconnected-(J1-GP22-Pad15)") (class "Default")
      (node (ref "J1") (pin "15") (pinfunction "GP22_15") (pintype "bidirectional"))
    )
    (net (code "82") (name "unconnected-(J1-GP23-Pad16)") (class "Default")
      (node (ref "J1") (pin "16") (pinfunction "GP23_16") (pintype "bidirectional"))
    )
    (net (code "83") (name "unconnected-(J1-GP26-Pad37)") (class "Default")
      (node (ref "J1") (pin "37") (pinfunction "GP26_37") (pintype "bidirectional"))
    )
    (net (code "84") (name "unconnected-(J1-GP27-Pad13)") (class "Default")
      (node (ref "J1") (pin "13") (pinfunction "GP27_13") (pintype "bidirectional"))
    )
    (net (code "85") (name "unconnected-(J1-ID_SC-Pad28)") (class "Default")
      (node (ref "J1") (pin "28") (pinfunction "ID_SC_28") (pintype "bidirectional"))
    )
    (net (code "86") (name "unconnected-(J1-ID_SD-Pad27)") (class "Default")
      (node (ref "J1") (pin "27") (pinfunction "ID_SD_27") (pintype "bidirectional"))
    )
    (net (code "87") (name "unconnected-(Q2-OE-Pad1)") (class "Default")
      (node (ref "Q2") (pin "1") (pinfunction "OE_1") (pintype "input"))
    )
    (net (code "88") (name "unconnected-(U$1-D3-PadP$14)") (class "Default")
      (node (ref "U$1") (pin "P$14") (pinfunction "D3_P$14") (pintype "bidirectional"))
    )
    (net (code "89") (name "unconnected-(U$1-REF3-PadP$18)") (class "Default")
      (node (ref "U$1") (pin "P$18") (pinfunction "REF3_P$18") (pintype "bidirectional"))
    )
    (net (code "90") (name "unconnected-(U$1-REFR1-PadP$17)") (class "Default")
      (node (ref "U$1") (pin "P$17") (pinfunction "REFR1_P$17") (pintype "bidirectional"))
    )
    (net (code "91") (name "unconnected-(U$1-REFR2-PadP$22)") (class "Default")
      (node (ref "U$1") (pin "P$22") (pinfunction "REFR2_P$22") (pintype "bidirectional"))
    )
    (net (code "92") (name "unconnected-(U$1-REFR3-PadP$21)") (class "Default")
      (node (ref "U$1") (pin "P$21") (pinfunction "REFR3_P$21") (pintype "bidirectional"))
    )
    (net (code "93") (name "unconnected-(U$1-S3-PadP$13)") (class "Default")
      (node (ref "U$1") (pin "P$13") (pinfunction "S3_P$13") (pintype "bidirectional"))
    )
    (net (code "94") (name "unconnected-(U2-FILT-Pad6)") (class "Default")
      (node (ref "U2") (pin "6") (pinfunction "FILT_6") (pintype "bidirectional"))
    )
  )
)
